# soraduino_lite.net
KiCad netlist of a schematic drawn in EAGLE
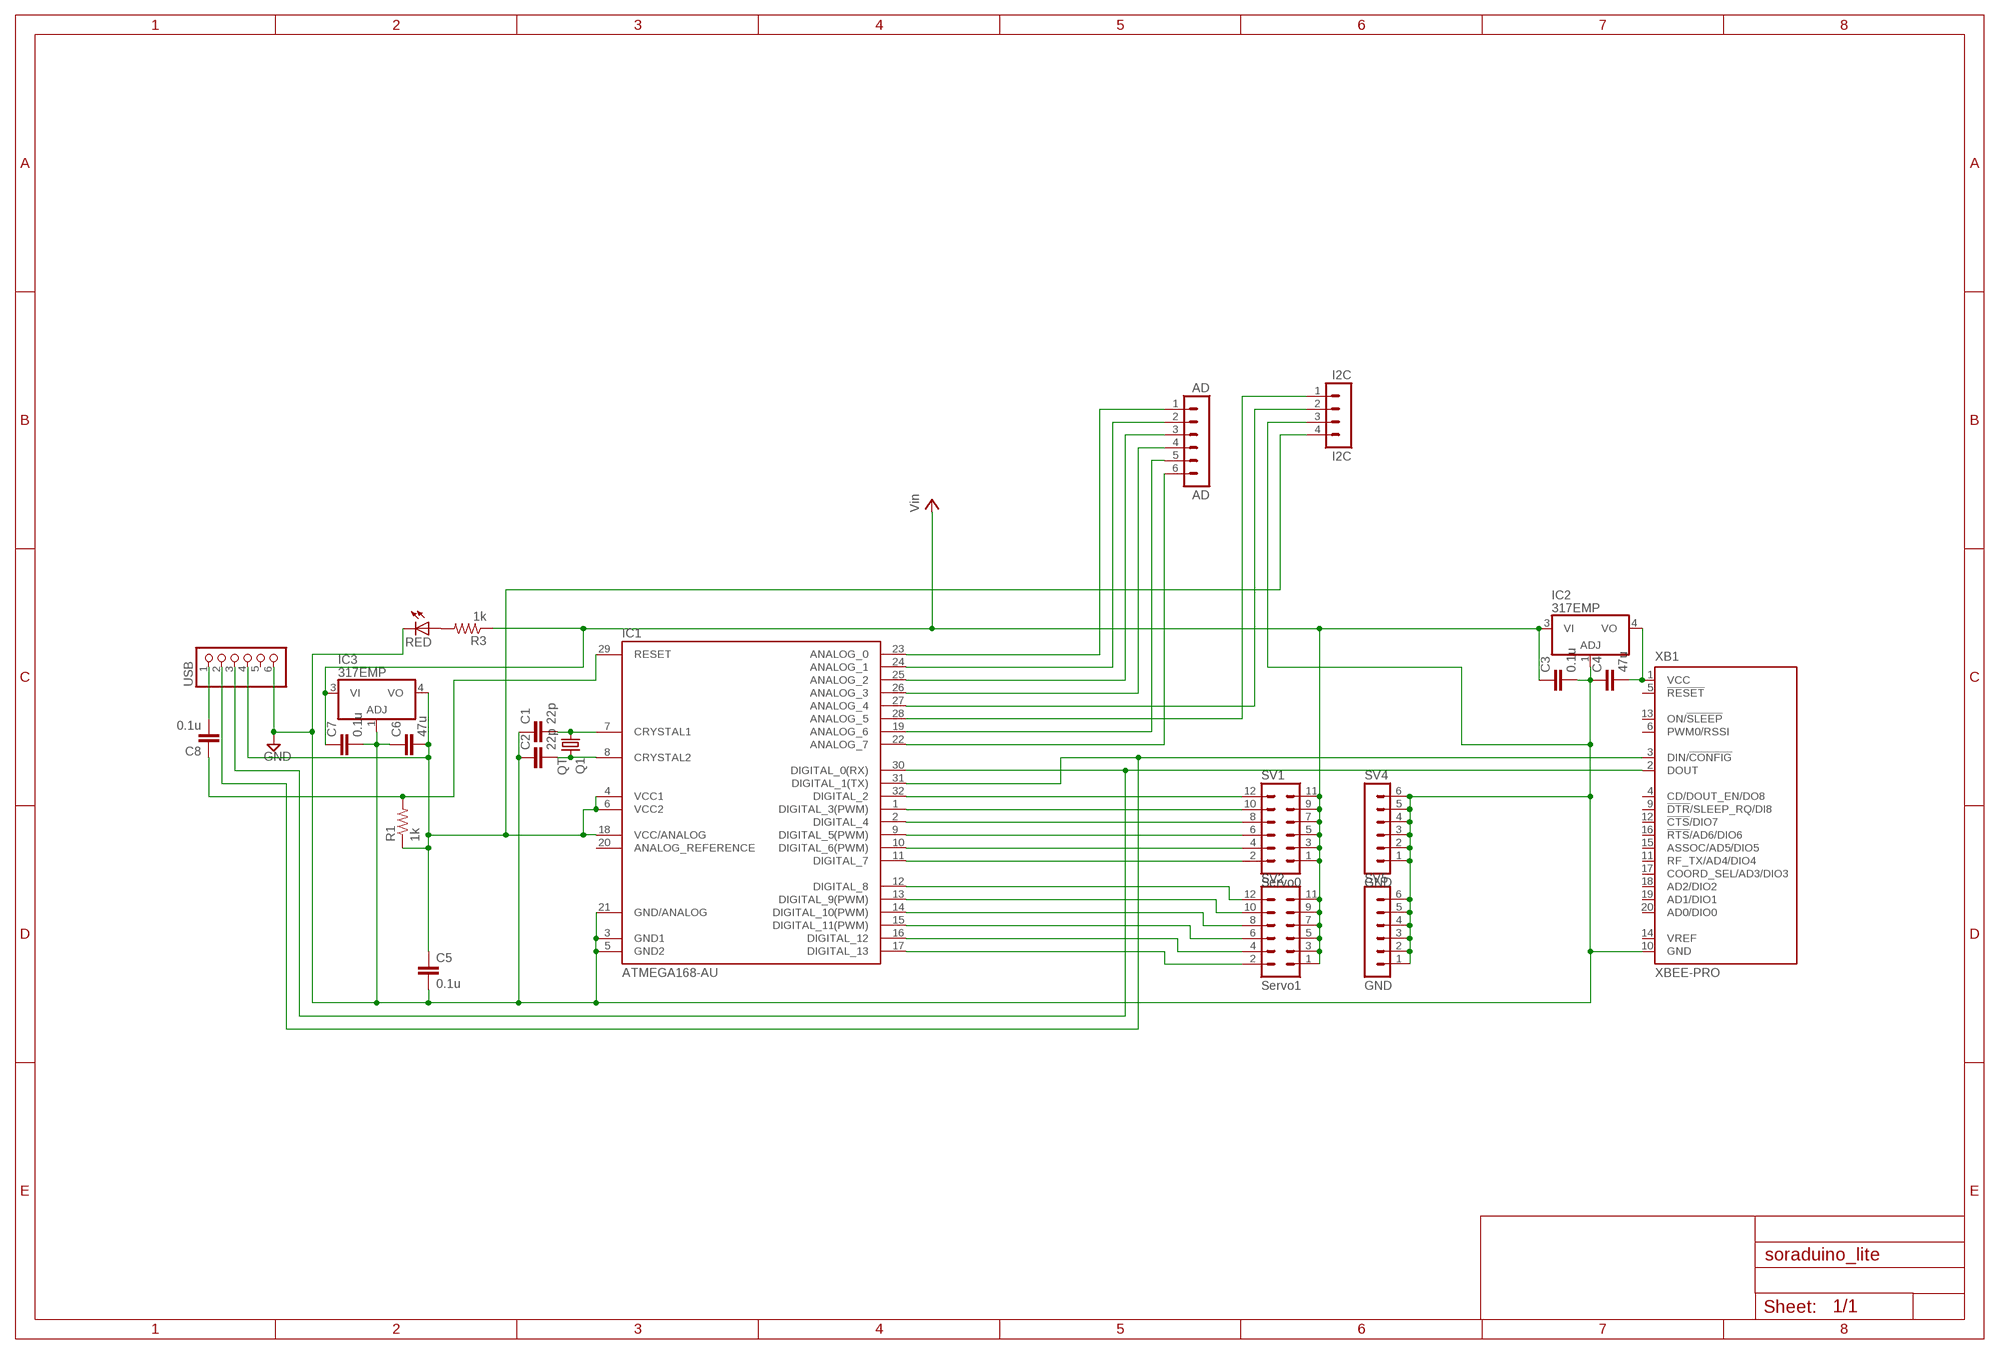
[diagram p0: schematic, sheet 1]

(export (version "E")
  (design (tool "Eeschema 10.0.6"))
  (components
    (comp (ref "AD")
      (value "AD")
      (footprint "eagle-import:MA06-1")
      (libsource (lib "eagle-import") (part "MA06-1"))
    )
    (comp (ref "C1")
      (value "22p")
      (footprint "eagle-import:C050-024X044")
      (libsource (lib "eagle-import") (part "C-EU050-024X044"))
    )
    (comp (ref "C2")
      (value "22p")
      (footprint "eagle-import:C050-024X044")
      (libsource (lib "eagle-import") (part "C-EU050-024X044"))
    )
    (comp (ref "C3")
      (value "0.1u")
      (footprint "eagle-import:C0805K")
      (libsource (lib "eagle-import") (part "resistor_C-EUC0805K"))
    )
    (comp (ref "C4")
      (value "47u")
      (footprint "eagle-import:C0805K")
      (libsource (lib "eagle-import") (part "resistor_C-EUC0805K"))
    )
    (comp (ref "C5")
      (value "0.1u")
      (footprint "eagle-import:C0805K")
      (libsource (lib "eagle-import") (part "resistor_C-EUC0805K"))
    )
    (comp (ref "C6")
      (value "47u")
      (footprint "eagle-import:C0805K")
      (libsource (lib "eagle-import") (part "resistor_C-EUC0805K"))
    )
    (comp (ref "C7")
      (value "0.1u")
      (footprint "eagle-import:C0805K")
      (libsource (lib "eagle-import") (part "resistor_C-EUC0805K"))
    )
    (comp (ref "C8")
      (value "0.1u")
      (footprint "eagle-import:C0805K")
      (libsource (lib "eagle-import") (part "resistor_C-EUC0805K"))
    )
    (comp (ref "I2C")
      (value "I2C")
      (footprint "eagle-import:MA04-1")
      (libsource (lib "eagle-import") (part "MA04-1"))
    )
    (comp (ref "IC1")
      (value "ATMEGA168-AU")
      (footprint "eagle-import:TQFP32-08")
      (libsource (lib "eagle-import") (part "ATMEGA168-AU"))
    )
    (comp (ref "IC2")
      (value "317EMP")
      (footprint "eagle-import:SOT223")
      (libsource (lib "eagle-import") (part "317EMP"))
    )
    (comp (ref "IC3")
      (value "317EMP")
      (footprint "eagle-import:SOT223")
      (libsource (lib "eagle-import") (part "317EMP"))
    )
    (comp (ref "Q1")
      (value "QT")
      (footprint "eagle-import:HC49_S")
      (libsource (lib "eagle-import") (part "CRYSTALHC49S"))
    )
    (comp (ref "R1")
      (value "1k")
      (footprint "eagle-import:R0603")
      (libsource (lib "eagle-import") (part "R-US_R0603"))
    )
    (comp (ref "R3")
      (value "1k")
      (footprint "eagle-import:R0603")
      (libsource (lib "eagle-import") (part "R-US_R0603"))
    )
    (comp (ref "RED")
      (value "LEDCHIPLED_1206")
      (footprint "eagle-import:CHIPLED_1206")
      (libsource (lib "eagle-import") (part "LEDCHIPLED_1206"))
    )
    (comp (ref "SV1")
      (value "Servo0")
      (footprint "eagle-import:MA06-2")
      (libsource (lib "eagle-import") (part "MA06-2"))
    )
    (comp (ref "SV2")
      (value "Servo1")
      (footprint "eagle-import:MA06-2")
      (libsource (lib "eagle-import") (part "MA06-2"))
    )
    (comp (ref "SV4")
      (value "GND")
      (footprint "eagle-import:MA06-1")
      (libsource (lib "eagle-import") (part "MA06-1"))
    )
    (comp (ref "SV5")
      (value "GND")
      (footprint "eagle-import:MA06-1")
      (libsource (lib "eagle-import") (part "MA06-1"))
    )
    (comp (ref "USB")
      (value "PINHD-1X6")
      (footprint "eagle-import:1X06")
      (libsource (lib "eagle-import") (part "PINHD-1X6"))
    )
    (comp (ref "XB1")
      (value "XBEE-PRO")
      (footprint "eagle-import:XBEE-PRO")
      (fields (field (name "MPN") "XBP24-AWI-001"))
      (libsource (lib "eagle-import") (part "XBEE-PRO"))
    )
  )
  (nets
    (net (code "1") (name "GND") (class "Default")
      (node (ref "C1") (pin "1") (pinfunction "1_1") (pintype "passive"))
      (node (ref "C2") (pin "1") (pinfunction "1_1") (pintype "passive"))
      (node (ref "C3") (pin "2") (pinfunction "2_2") (pintype "passive"))
      (node (ref "C4") (pin "1") (pinfunction "1_1") (pintype "passive"))
      (node (ref "C5") (pin "2") (pinfunction "2_2") (pintype "passive"))
      (node (ref "C6") (pin "1") (pinfunction "1_1") (pintype "passive"))
      (node (ref "C7") (pin "2") (pinfunction "2_2") (pintype "passive"))
      (node (ref "I2C") (pin "3") (pinfunction "3_3") (pintype "passive"))
      (node (ref "IC1") (pin "21") (pinfunction "GND/ANALOG_21") (pintype "power_in"))
      (node (ref "IC1") (pin "3") (pinfunction "GND1_3") (pintype "power_in"))
      (node (ref "IC1") (pin "5") (pinfunction "GND2_5") (pintype "power_in"))
      (node (ref "IC2") (pin "1") (pinfunction "ADJ_1") (pintype "input"))
      (node (ref "IC3") (pin "1") (pinfunction "ADJ_1") (pintype "input"))
      (node (ref "RED") (pin "C") (pinfunction "C_C") (pintype "passive"))
      (node (ref "SV4") (pin "1") (pinfunction "1_1") (pintype "passive"))
      (node (ref "SV4") (pin "2") (pinfunction "2_2") (pintype "passive"))
      (node (ref "SV4") (pin "3") (pinfunction "3_3") (pintype "passive"))
      (node (ref "SV4") (pin "4") (pinfunction "4_4") (pintype "passive"))
      (node (ref "SV4") (pin "5") (pinfunction "5_5") (pintype "passive"))
      (node (ref "SV4") (pin "6") (pinfunction "6_6") (pintype "passive"))
      (node (ref "SV5") (pin "1") (pinfunction "1_1") (pintype "passive"))
      (node (ref "SV5") (pin "2") (pinfunction "2_2") (pintype "passive"))
      (node (ref "SV5") (pin "3") (pinfunction "3_3") (pintype "passive"))
      (node (ref "SV5") (pin "4") (pinfunction "4_4") (pintype "passive"))
      (node (ref "SV5") (pin "5") (pinfunction "5_5") (pintype "passive"))
      (node (ref "SV5") (pin "6") (pinfunction "6_6") (pintype "passive"))
      (node (ref "USB") (pin "6") (pinfunction "6_6") (pintype "passive"))
      (node (ref "XB1") (pin "10") (pinfunction "GND_10") (pintype "power_in"))
    )
    (net (code "2") (name "Net-(C8-Pad2)") (class "Default")
      (node (ref "C8") (pin "2") (pinfunction "2_2") (pintype "passive"))
      (node (ref "USB") (pin "1") (pinfunction "1_1") (pintype "passive"))
    )
    (net (code "3") (name "Net-(IC1-ANALOG_0)") (class "Default")
      (node (ref "AD") (pin "1") (pinfunction "1_1") (pintype "passive"))
      (node (ref "IC1") (pin "23") (pinfunction "ANALOG_0_23") (pintype "bidirectional"))
    )
    (net (code "4") (name "Net-(IC1-ANALOG_1)") (class "Default")
      (node (ref "AD") (pin "2") (pinfunction "2_2") (pintype "passive"))
      (node (ref "IC1") (pin "24") (pinfunction "ANALOG_1_24") (pintype "bidirectional"))
    )
    (net (code "5") (name "Net-(IC1-ANALOG_2)") (class "Default")
      (node (ref "AD") (pin "3") (pinfunction "3_3") (pintype "passive"))
      (node (ref "IC1") (pin "25") (pinfunction "ANALOG_2_25") (pintype "bidirectional"))
    )
    (net (code "6") (name "Net-(IC1-ANALOG_3)") (class "Default")
      (node (ref "AD") (pin "4") (pinfunction "4_4") (pintype "passive"))
      (node (ref "IC1") (pin "26") (pinfunction "ANALOG_3_26") (pintype "bidirectional"))
    )
    (net (code "7") (name "Net-(IC1-ANALOG_4)") (class "Default")
      (node (ref "I2C") (pin "2") (pinfunction "2_2") (pintype "passive"))
      (node (ref "IC1") (pin "27") (pinfunction "ANALOG_4_27") (pintype "bidirectional"))
    )
    (net (code "8") (name "Net-(IC1-ANALOG_5)") (class "Default")
      (node (ref "I2C") (pin "1") (pinfunction "1_1") (pintype "passive"))
      (node (ref "IC1") (pin "28") (pinfunction "ANALOG_5_28") (pintype "bidirectional"))
    )
    (net (code "9") (name "Net-(IC1-ANALOG_6)") (class "Default")
      (node (ref "AD") (pin "5") (pinfunction "5_5") (pintype "passive"))
      (node (ref "IC1") (pin "19") (pinfunction "ANALOG_6_19") (pintype "passive"))
    )
    (net (code "10") (name "Net-(IC1-ANALOG_7)") (class "Default")
      (node (ref "AD") (pin "6") (pinfunction "6_6") (pintype "passive"))
      (node (ref "IC1") (pin "22") (pinfunction "ANALOG_7_22") (pintype "passive"))
    )
    (net (code "11") (name "Net-(IC1-CRYSTAL1)") (class "Default")
      (node (ref "C1") (pin "2") (pinfunction "2_2") (pintype "passive"))
      (node (ref "IC1") (pin "7") (pinfunction "CRYSTAL1_7") (pintype "bidirectional"))
      (node (ref "Q1") (pin "1") (pinfunction "1_1") (pintype "passive"))
    )
    (net (code "12") (name "Net-(IC1-CRYSTAL2)") (class "Default")
      (node (ref "C2") (pin "2") (pinfunction "2_2") (pintype "passive"))
      (node (ref "IC1") (pin "8") (pinfunction "CRYSTAL2_8") (pintype "bidirectional"))
      (node (ref "Q1") (pin "2") (pinfunction "2_2") (pintype "passive"))
    )
    (net (code "13") (name "Net-(IC1-DIGITAL_0(RX))") (class "Default")
      (node (ref "IC1") (pin "30") (pinfunction "DIGITAL_0(RX)_30") (pintype "bidirectional"))
      (node (ref "USB") (pin "3") (pinfunction "3_3") (pintype "passive"))
      (node (ref "XB1") (pin "2") (pinfunction "DOUT_2") (pintype "output"))
    )
    (net (code "14") (name "Net-(IC1-DIGITAL_1(TX))") (class "Default")
      (node (ref "IC1") (pin "31") (pinfunction "DIGITAL_1(TX)_31") (pintype "bidirectional"))
      (node (ref "USB") (pin "2") (pinfunction "2_2") (pintype "passive"))
      (node (ref "XB1") (pin "3") (pinfunction "DIN/~{CONFIG}_3") (pintype "input"))
    )
    (net (code "15") (name "Net-(IC1-DIGITAL_2)") (class "Default")
      (node (ref "IC1") (pin "32") (pinfunction "DIGITAL_2_32") (pintype "bidirectional"))
      (node (ref "SV1") (pin "12") (pinfunction "12_12") (pintype "passive"))
    )
    (net (code "16") (name "Net-(IC1-DIGITAL_3(PWM))") (class "Default")
      (node (ref "IC1") (pin "1") (pinfunction "DIGITAL_3(PWM)_1") (pintype "bidirectional"))
      (node (ref "SV1") (pin "10") (pinfunction "10_10") (pintype "passive"))
    )
    (net (code "17") (name "Net-(IC1-DIGITAL_4)") (class "Default")
      (node (ref "IC1") (pin "2") (pinfunction "DIGITAL_4_2") (pintype "bidirectional"))
      (node (ref "SV1") (pin "8") (pinfunction "8_8") (pintype "passive"))
    )
    (net (code "18") (name "Net-(IC1-DIGITAL_5(PWM))") (class "Default")
      (node (ref "IC1") (pin "9") (pinfunction "DIGITAL_5(PWM)_9") (pintype "bidirectional"))
      (node (ref "SV1") (pin "6") (pinfunction "6_6") (pintype "passive"))
    )
    (net (code "19") (name "Net-(IC1-DIGITAL_6(PWM))") (class "Default")
      (node (ref "IC1") (pin "10") (pinfunction "DIGITAL_6(PWM)_10") (pintype "bidirectional"))
      (node (ref "SV1") (pin "4") (pinfunction "4_4") (pintype "passive"))
    )
    (net (code "20") (name "Net-(IC1-DIGITAL_7)") (class "Default")
      (node (ref "IC1") (pin "11") (pinfunction "DIGITAL_7_11") (pintype "bidirectional"))
      (node (ref "SV1") (pin "2") (pinfunction "2_2") (pintype "passive"))
    )
    (net (code "21") (name "Net-(IC1-DIGITAL_8)") (class "Default")
      (node (ref "IC1") (pin "12") (pinfunction "DIGITAL_8_12") (pintype "bidirectional"))
      (node (ref "SV2") (pin "12") (pinfunction "12_12") (pintype "passive"))
    )
    (net (code "22") (name "Net-(IC1-DIGITAL_9(PWM))") (class "Default")
      (node (ref "IC1") (pin "13") (pinfunction "DIGITAL_9(PWM)_13") (pintype "bidirectional"))
      (node (ref "SV2") (pin "10") (pinfunction "10_10") (pintype "passive"))
    )
    (net (code "23") (name "Net-(IC1-DIGITAL_10(PWM))") (class "Default")
      (node (ref "IC1") (pin "14") (pinfunction "DIGITAL_10(PWM)_14") (pintype "bidirectional"))
      (node (ref "SV2") (pin "8") (pinfunction "8_8") (pintype "passive"))
    )
    (net (code "24") (name "Net-(IC1-DIGITAL_11(PWM))") (class "Default")
      (node (ref "IC1") (pin "15") (pinfunction "DIGITAL_11(PWM)_15") (pintype "bidirectional"))
      (node (ref "SV2") (pin "6") (pinfunction "6_6") (pintype "passive"))
    )
    (net (code "25") (name "Net-(IC1-DIGITAL_12)") (class "Default")
      (node (ref "IC1") (pin "16") (pinfunction "DIGITAL_12_16") (pintype "bidirectional"))
      (node (ref "SV2") (pin "4") (pinfunction "4_4") (pintype "passive"))
    )
    (net (code "26") (name "Net-(IC1-DIGITAL_13)") (class "Default")
      (node (ref "IC1") (pin "17") (pinfunction "DIGITAL_13_17") (pintype "bidirectional"))
      (node (ref "SV2") (pin "2") (pinfunction "2_2") (pintype "passive"))
    )
    (net (code "27") (name "Net-(IC1-RESET)") (class "Default")
      (node (ref "C8") (pin "1") (pinfunction "1_1") (pintype "passive"))
      (node (ref "IC1") (pin "29") (pinfunction "RESET_29") (pintype "bidirectional"))
      (node (ref "R1") (pin "2") (pinfunction "2_2") (pintype "passive"))
    )
    (net (code "28") (name "Net-(IC1-VCC1)") (class "Default")
      (node (ref "C5") (pin "1") (pinfunction "1_1") (pintype "passive"))
      (node (ref "C6") (pin "2") (pinfunction "2_2") (pintype "passive"))
      (node (ref "I2C") (pin "4") (pinfunction "4_4") (pintype "passive"))
      (node (ref "IC1") (pin "18") (pinfunction "VCC/ANALOG_18") (pintype "passive"))
      (node (ref "IC1") (pin "4") (pinfunction "VCC1_4") (pintype "power_in"))
      (node (ref "IC1") (pin "6") (pinfunction "VCC2_6") (pintype "power_in"))
      (node (ref "IC3") (pin "4") (pinfunction "VO_4") (pintype "passive"))
      (node (ref "R1") (pin "1") (pinfunction "1_1") (pintype "passive"))
      (node (ref "USB") (pin "4") (pinfunction "4_4") (pintype "passive"))
    )
    (net (code "29") (name "Net-(IC2-VO)") (class "Default")
      (node (ref "C4") (pin "2") (pinfunction "2_2") (pintype "passive"))
      (node (ref "IC2") (pin "4") (pinfunction "VO_4") (pintype "passive"))
      (node (ref "XB1") (pin "1") (pinfunction "VCC_1") (pintype "power_in"))
    )
    (net (code "30") (name "Net-(R3-Pad2)") (class "Default")
      (node (ref "R3") (pin "2") (pinfunction "2_2") (pintype "passive"))
      (node (ref "RED") (pin "A") (pinfunction "A_A") (pintype "passive"))
    )
    (net (code "31") (name "Vin") (class "Default")
      (node (ref "C3") (pin "1") (pinfunction "1_1") (pintype "passive"))
      (node (ref "C7") (pin "1") (pinfunction "1_1") (pintype "passive"))
      (node (ref "IC2") (pin "3") (pinfunction "VI_3") (pintype "input"))
      (node (ref "IC3") (pin "3") (pinfunction "VI_3") (pintype "input"))
      (node (ref "R3") (pin "1") (pinfunction "1_1") (pintype "passive"))
      (node (ref "SV1") (pin "1") (pinfunction "1_1") (pintype "passive"))
      (node (ref "SV1") (pin "11") (pinfunction "11_11") (pintype "passive"))
      (node (ref "SV1") (pin "3") (pinfunction "3_3") (pintype "passive"))
      (node (ref "SV1") (pin "5") (pinfunction "5_5") (pintype "passive"))
      (node (ref "SV1") (pin "7") (pinfunction "7_7") (pintype "passive"))
      (node (ref "SV1") (pin "9") (pinfunction "9_9") (pintype "passive"))
      (node (ref "SV2") (pin "1") (pinfunction "1_1") (pintype "passive"))
      (node (ref "SV2") (pin "11") (pinfunction "11_11") (pintype "passive"))
      (node (ref "SV2") (pin "3") (pinfunction "3_3") (pintype "passive"))
      (node (ref "SV2") (pin "5") (pinfunction "5_5") (pintype "passive"))
      (node (ref "SV2") (pin "7") (pinfunction "7_7") (pintype "passive"))
      (node (ref "SV2") (pin "9") (pinfunction "9_9") (pintype "passive"))
    )
    (net (code "32") (name "unconnected-(IC1-ANALOG_REFERENCE-Pad20)") (class "Default")
      (node (ref "IC1") (pin "20") (pinfunction "ANALOG_REFERENCE_20") (pintype "passive"))
    )
    (net (code "33") (name "unconnected-(USB-Pad5)") (class "Default")
      (node (ref "USB") (pin "5") (pinfunction "5_5") (pintype "passive"))
    )
    (net (code "34") (name "unconnected-(XB1-AD0{slash}DIO0-Pad20)") (class "Default")
      (node (ref "XB1") (pin "20") (pinfunction "AD0/DIO0_20") (pintype "bidirectional"))
    )
    (net (code "35") (name "unconnected-(XB1-AD1{slash}DIO1-Pad19)") (class "Default")
      (node (ref "XB1") (pin "19") (pinfunction "AD1/DIO1_19") (pintype "bidirectional"))
    )
    (net (code "36") (name "unconnected-(XB1-AD2{slash}DIO2-Pad18)") (class "Default")
      (node (ref "XB1") (pin "18") (pinfunction "AD2/DIO2_18") (pintype "bidirectional"))
    )
    (net (code "37") (name "unconnected-(XB1-ASSOC{slash}AD5{slash}DIO5-Pad15)") (class "Default")
      (node (ref "XB1") (pin "15") (pinfunction "ASSOC/AD5/DIO5_15") (pintype "bidirectional"))
    )
    (net (code "38") (name "unconnected-(XB1-CD{slash}DOUT_EN{slash}DO8-Pad4)") (class "Default")
      (node (ref "XB1") (pin "4") (pinfunction "CD/DOUT_EN/DO8_4") (pintype "output"))
    )
    (net (code "39") (name "unconnected-(XB1-COORD_SEL{slash}AD3{slash}DIO3-Pad17)") (class "Default")
      (node (ref "XB1") (pin "17") (pinfunction "COORD_SEL/AD3/DIO3_17") (pintype "bidirectional"))
    )
    (net (code "40") (name "unconnected-(XB1-ON{slash}~{SLEEP}-Pad13)") (class "Default")
      (node (ref "XB1") (pin "13") (pinfunction "ON/~{SLEEP}_13") (pintype "output"))
    )
    (net (code "41") (name "unconnected-(XB1-PWM0{slash}RSSI-Pad6)") (class "Default")
      (node (ref "XB1") (pin "6") (pinfunction "PWM0/RSSI_6") (pintype "output"))
    )
    (net (code "42") (name "unconnected-(XB1-RF_TX{slash}AD4{slash}DIO4-Pad11)") (class "Default")
      (node (ref "XB1") (pin "11") (pinfunction "RF_TX/AD4/DIO4_11") (pintype "bidirectional"))
    )
    (net (code "43") (name "unconnected-(XB1-VREF-Pad14)") (class "Default")
      (node (ref "XB1") (pin "14") (pinfunction "VREF_14") (pintype "input"))
    )
    (net (code "44") (name "unconnected-(XB1-~{CTS}{slash}DIO7-Pad12)") (class "Default")
      (node (ref "XB1") (pin "12") (pinfunction "~{CTS}/DIO7_12") (pintype "bidirectional"))
    )
    (net (code "45") (name "unconnected-(XB1-~{DTR}{slash}SLEEP_RQ{slash}DI8-Pad9)") (class "Default")
      (node (ref "XB1") (pin "9") (pinfunction "~{DTR}/SLEEP_RQ/DI8_9") (pintype "bidirectional"))
    )
    (net (code "46") (name "unconnected-(XB1-~{RESET}-Pad5)") (class "Default")
      (node (ref "XB1") (pin "5") (pinfunction "~{RESET}_5") (pintype "input"))
    )
    (net (code "47") (name "unconnected-(XB1-~{RTS}{slash}AD6{slash}DIO6-Pad16)") (class "Default")
      (node (ref "XB1") (pin "16") (pinfunction "~{RTS}/AD6/DIO6_16") (pintype "bidirectional"))
    )
  )
)
